# Cell.net
KiCad netlist of a schematic drawn in Altium Designer
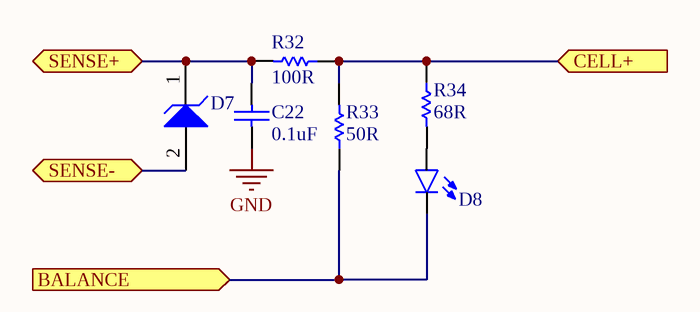
[diagram p0: Cell.SchDoc]

(export (version "E")
  (design (tool "Eeschema 10.0.6"))
  (components
    (comp (ref "C22")
      (value "0.1uF")
      (footprint "C0402[1005X55]")
      (description "0.1uF 6.3V 10% 0402 (1005 Metric)")
      (fields (field (name "TOLERANCE") "10%") (field (name "PARTNUMBER") "GRM155R70J104KA01D"))
      (libsource (lib "Capacitors") (part "CAP_0.1uF_6.3V_0402_10%"))
    )
    (comp (ref "D7")
      (value "MM3Z12VT1G")
      (footprint "ONSC-SOD-323-2-477-02_V")
      (description "Zener Voltage Regulator, 300 mW, 2-Pin SOD-323, Tape and Reel")
      (fields (field (name "MANUFACTURER") "On Semiconductor") (field (name "PARTNUMBER") "MM3Z12VT1"))
      (libsource (lib "Altium Content Vault") (part "CMP-1060-00726-1"))
    )
    (comp (ref "D8")
      (value "LED_0603")
      (footprint "LED0603")
      (fields (field (name "PARTNUMBER") "LTST-C193TBKT-5A") (field (name "MANUFACTURER") "Lite-On Inc."))
      (libsource (lib "LEDs-0603") (part "LED_0603"))
    )
    (comp (ref "R32")
      (value "100R")
      (footprint "R0402[1005]")
      (description "100R 0.063W 1% 0402 (1005 Metric)")
      (fields (field (name "POWER") "0.063W") (field (name "TOLERANCE") "1%"))
      (libsource (lib "Resistors") (part "RES_100R_0402_1%"))
    )
    (comp (ref "R33")
      (value "50R")
      (footprint "RESC0603(1608)_L")
      (description "50R 1.5W 5% 0603 (1608 Metric)  SMD")
      (fields (field (name "TOLERANCE") "5 %") (field (name "POWER") "1.5 W"))
      (libsource (lib "Altium Content Vault") (part "CMP-1012-00043-1"))
    )
    (comp (ref "R34")
      (value "68R")
      (footprint "R0402[1005]")
      (description "68R 0.063W 1% 0402 (1005 Metric)")
      (fields (field (name "MANUFACTURER") "KOA Speer") (field (name "PARTNUMBER") "RK73H1ETTP68R0F"))
      (libsource (lib "Resistors") (part "RES_68R_0402_1%"))
    )
  )
  (nets
    (net (code "1") (name "/BALANCE") (class "Default")
      (node (ref "D8") (pin "C") (pinfunction "C_C") (pintype "passive"))
      (node (ref "R33") (pin "1") (pinfunction "1_1") (pintype "passive"))
    )
    (net (code "2") (name "/CELL+") (class "Default")
      (node (ref "R32") (pin "2") (pinfunction "2_2") (pintype "passive"))
      (node (ref "R33") (pin "2") (pinfunction "2_2") (pintype "passive"))
      (node (ref "R34") (pin "2") (pinfunction "2_2") (pintype "passive"))
    )
    (net (code "3") (name "/SENSE+") (class "Default")
      (node (ref "C22") (pin "2") (pinfunction "2_2") (pintype "passive"))
      (node (ref "D7") (pin "1") (pinfunction "K_1") (pintype "passive"))
      (node (ref "R32") (pin "1") (pinfunction "1_1") (pintype "passive"))
    )
    (net (code "4") (name "/SENSE-") (class "Default")
      (node (ref "D7") (pin "2") (pinfunction "A_2") (pintype "passive"))
    )
    (net (code "5") (name "GND") (class "Default")
      (node (ref "C22") (pin "1") (pinfunction "1_1") (pintype "passive"))
    )
    (net (code "6") (name "Net-(D8-PadA)") (class "Default")
      (node (ref "D8") (pin "A") (pinfunction "A_A") (pintype "passive"))
      (node (ref "R34") (pin "1") (pinfunction "1_1") (pintype "passive"))
    )
  )
)
